# 9_-_STM32F407_Controller.net
KiCad netlist of a schematic drawn in Altium Designer
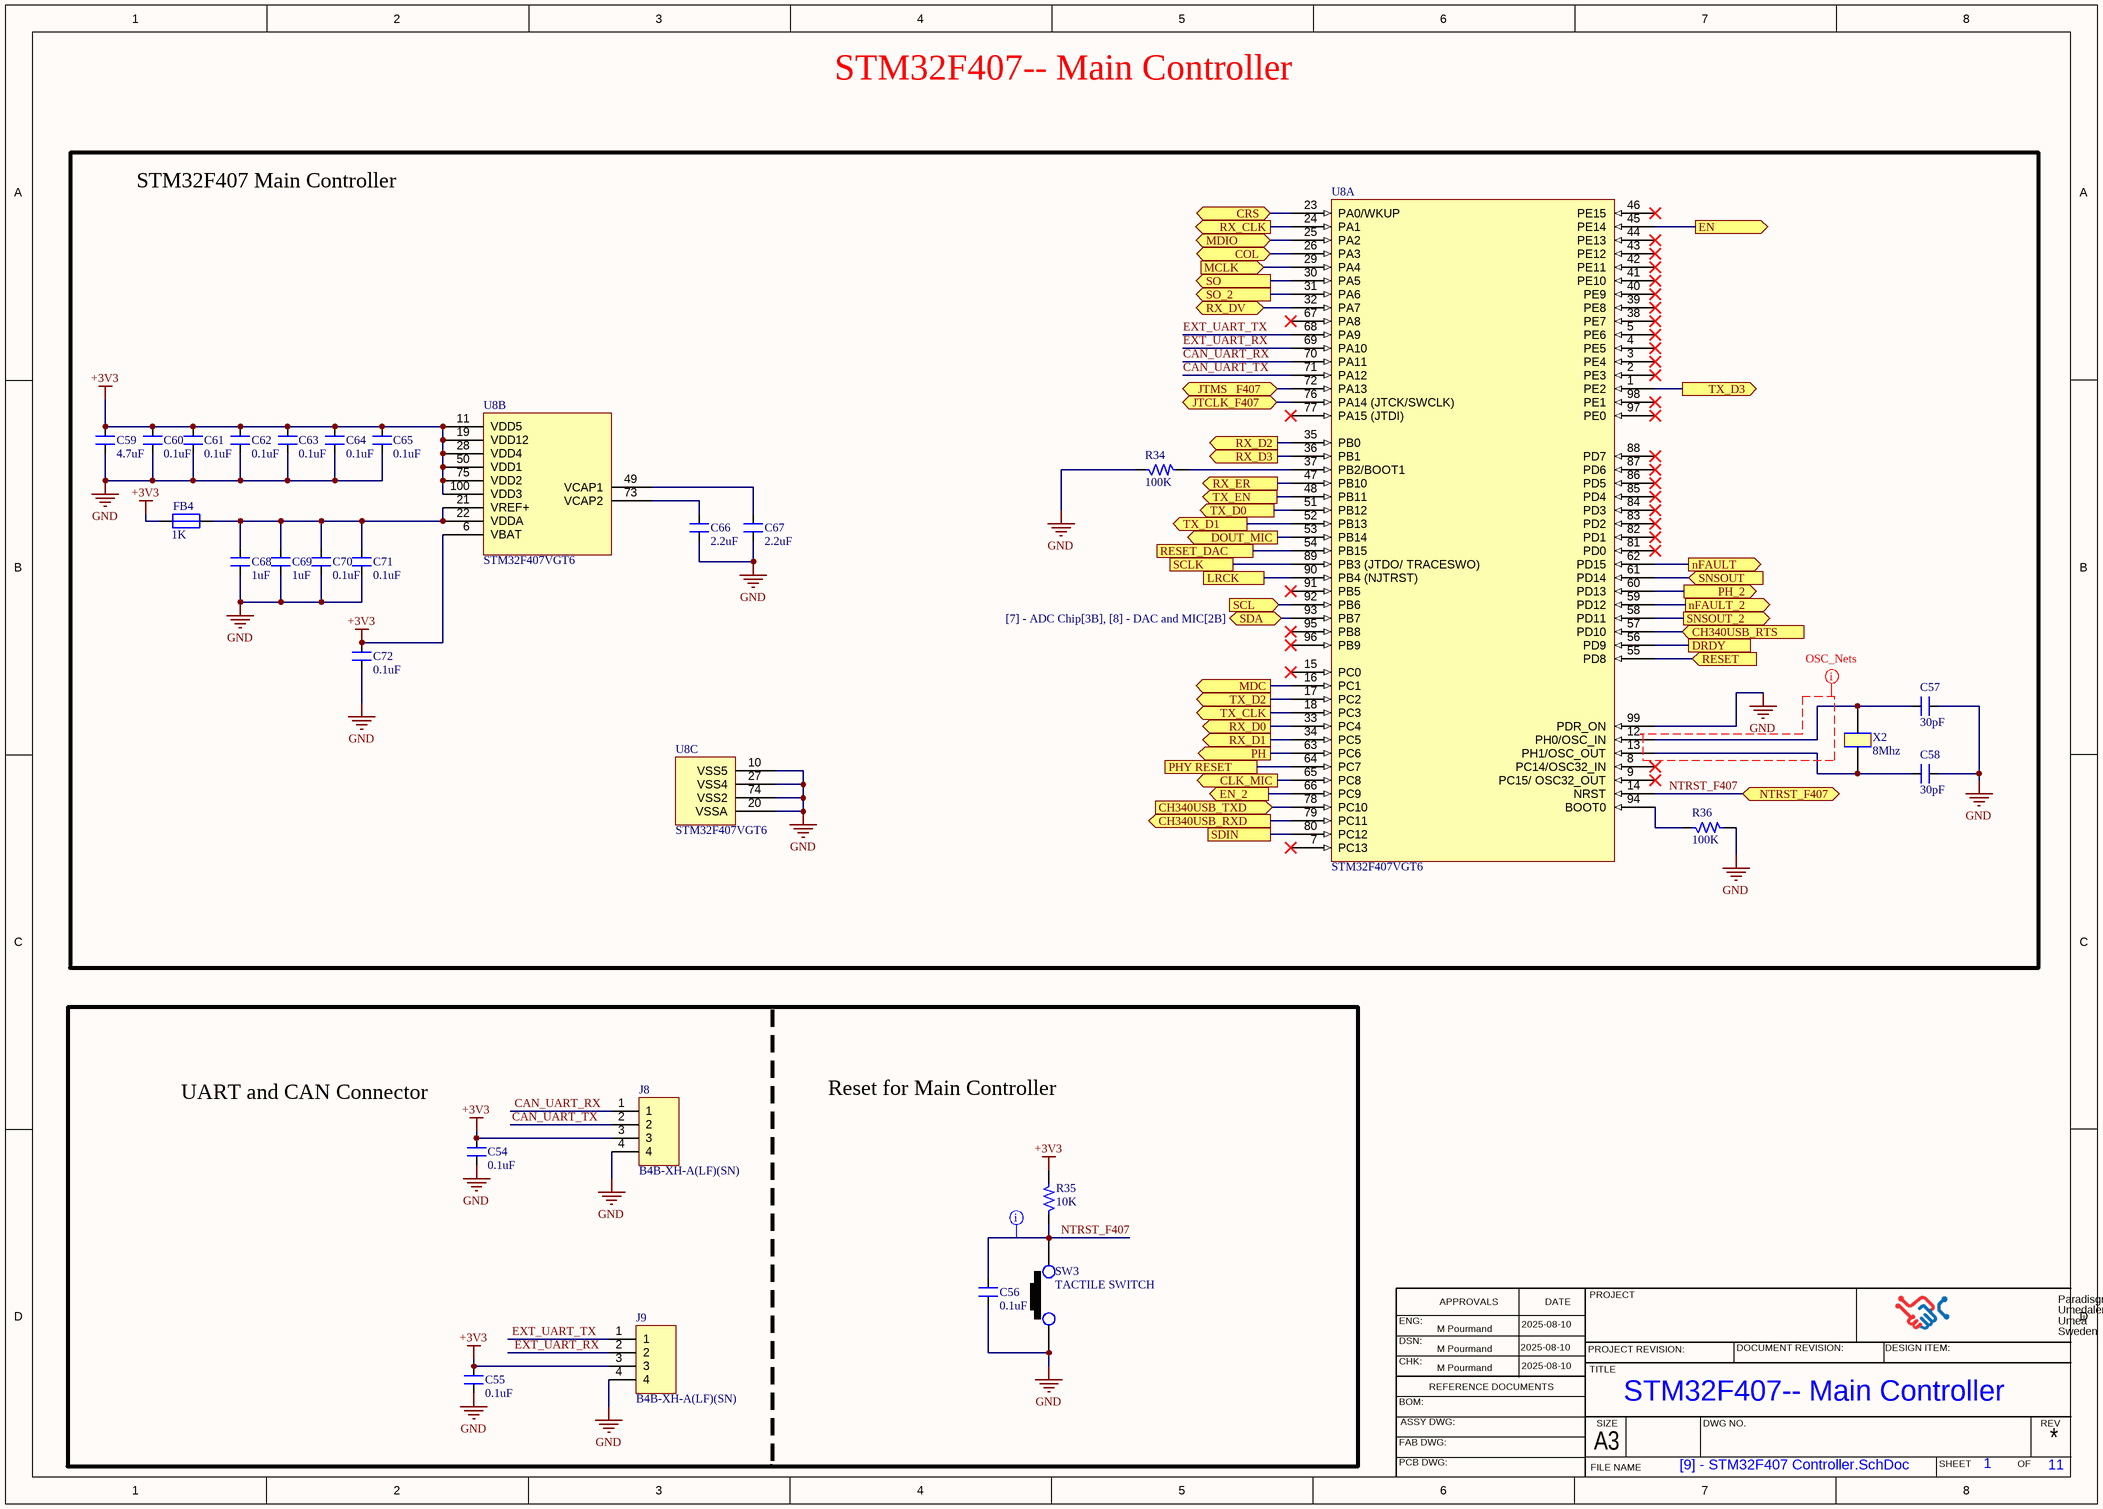
[diagram p0: [9] - STM32F407 Controller.SchDoc]

(export (version "E")
  (design (tool "Eeschema 10.0.6"))
  (components
    (comp (ref "C54")
      (value "0.1uF")
      (footprint "CAP_0805")
      (description "0.1µF ±10% 50V Ceramic Capacitor X7R 0805 (2012 Metric)")
      (fields
        (field (name "MANUFACTURER") "Samsung")
        (field (name "MANUFACTURER PART NUMBER") "CL21B104KBCNNNC")
      )
      (libsource (lib "ESTEEMPCBLIB") (part "CAP_0.1uF-50V-10%-0805"))
    )
    (comp (ref "C55")
      (value "0.1uF")
      (footprint "CAP_0805")
      (description "0.1µF ±10% 50V Ceramic Capacitor X7R 0805 (2012 Metric)")
      (fields
        (field (name "MANUFACTURER") "Samsung")
        (field (name "MANUFACTURER PART NUMBER") "CL21B104KBCNNNC")
      )
      (libsource (lib "ESTEEMPCBLIB") (part "CAP_0.1uF-50V-10%-0805"))
    )
    (comp (ref "C56")
      (value "0.1uF")
      (footprint "CAP_0805")
      (description "0.1µF ±10% 50V Ceramic Capacitor X7R 0805 (2012 Metric)")
      (fields
        (field (name "MANUFACTURER") "Samsung")
        (field (name "MANUFACTURER PART NUMBER") "CL21B104KBCNNNC")
      )
      (libsource (lib "ESTEEMPCBLIB") (part "CAP_0.1uF-50V-10%-0805"))
    )
    (comp (ref "C57")
      (value "30pF")
      (footprint "CAP_0805")
      (description "±10% 50V Ceramic Capacitor C0G, NP0 0805 (2012 Metric)")
      (fields
        (field (name "MANUFACTURER PART NUMBER") "C0805C300K5GAC7800")
        (field (name "MANUFACTURER") "KEMET")
      )
      (libsource (lib "ESTEEMPCBLIB") (part "CAP_30pF-50V-10%-0805"))
    )
    (comp (ref "C58")
      (value "30pF")
      (footprint "CAP_0805")
      (description "±10% 50V Ceramic Capacitor C0G, NP0 0805 (2012 Metric)")
      (fields
        (field (name "MANUFACTURER PART NUMBER") "C0805C300K5GAC7800")
        (field (name "MANUFACTURER") "KEMET")
      )
      (libsource (lib "ESTEEMPCBLIB") (part "CAP_30pF-50V-10%-0805"))
    )
    (comp (ref "C59")
      (value "4.7uF")
      (footprint "CAP_0805")
      (description "4.7µF ±10% 50V Ceramic Capacitor X5R 0805 (2012 Metric)")
      (fields
        (field (name "MANUFACTURER") "Yageo")
        (field (name "MANUFACTURER PART NUMBER") "GRM21BR61H475KE51L")
      )
      (libsource (lib "ESTEEMPCBLIB") (part "CAP_4.7uF-50V-10%-0805"))
    )
    (comp (ref "C60")
      (value "0.1uF")
      (footprint "CAP_0805")
      (description "0.1µF ±10% 50V Ceramic Capacitor X7R 0805 (2012 Metric)")
      (fields
        (field (name "MANUFACTURER") "Samsung")
        (field (name "MANUFACTURER PART NUMBER") "CL21B104KBCNNNC")
      )
      (libsource (lib "ESTEEMPCBLIB") (part "CAP_0.1uF-50V-10%-0805"))
    )
    (comp (ref "C61")
      (value "0.1uF")
      (footprint "CAP_0805")
      (description "0.1µF ±10% 50V Ceramic Capacitor X7R 0805 (2012 Metric)")
      (fields
        (field (name "MANUFACTURER") "Samsung")
        (field (name "MANUFACTURER PART NUMBER") "CL21B104KBCNNNC")
      )
      (libsource (lib "ESTEEMPCBLIB") (part "CAP_0.1uF-50V-10%-0805"))
    )
    (comp (ref "C62")
      (value "0.1uF")
      (footprint "CAP_0805")
      (description "0.1µF ±10% 50V Ceramic Capacitor X7R 0805 (2012 Metric)")
      (fields
        (field (name "MANUFACTURER") "Samsung")
        (field (name "MANUFACTURER PART NUMBER") "CL21B104KBCNNNC")
      )
      (libsource (lib "ESTEEMPCBLIB") (part "CAP_0.1uF-50V-10%-0805"))
    )
    (comp (ref "C63")
      (value "0.1uF")
      (footprint "CAP_0805")
      (description "0.1µF ±10% 50V Ceramic Capacitor X7R 0805 (2012 Metric)")
      (fields
        (field (name "MANUFACTURER") "Samsung")
        (field (name "MANUFACTURER PART NUMBER") "CL21B104KBCNNNC")
      )
      (libsource (lib "ESTEEMPCBLIB") (part "CAP_0.1uF-50V-10%-0805"))
    )
    (comp (ref "C64")
      (value "0.1uF")
      (footprint "CAP_0805")
      (description "0.1µF ±10% 50V Ceramic Capacitor X7R 0805 (2012 Metric)")
      (fields
        (field (name "MANUFACTURER") "Samsung")
        (field (name "MANUFACTURER PART NUMBER") "CL21B104KBCNNNC")
      )
      (libsource (lib "ESTEEMPCBLIB") (part "CAP_0.1uF-50V-10%-0805"))
    )
    (comp (ref "C65")
      (value "0.1uF")
      (footprint "CAP_0805")
      (description "0.1µF ±10% 50V Ceramic Capacitor X7R 0805 (2012 Metric)")
      (fields
        (field (name "MANUFACTURER") "Samsung")
        (field (name "MANUFACTURER PART NUMBER") "CL21B104KBCNNNC")
      )
      (libsource (lib "ESTEEMPCBLIB") (part "CAP_0.1uF-50V-10%-0805"))
    )
    (comp (ref "C66")
      (value "2.2uF")
      (footprint "CAP_0805")
      (description "2.2µF ±10% 25V Ceramic Capacitor X7R 0805 (2012 Metric)")
      (fields
        (field (name "MANUFACTURER") "KEMET")
        (field (name "MANUFACTURER PART NUMBER") "CL21B225KAFNFNE")
      )
      (libsource (lib "ESTEEMPCBLIB") (part "CAP_2.2uF-25V-10%-0805"))
    )
    (comp (ref "C67")
      (value "2.2uF")
      (footprint "CAP_0805")
      (description "2.2µF ±10% 25V Ceramic Capacitor X7R 0805 (2012 Metric)")
      (fields
        (field (name "MANUFACTURER") "KEMET")
        (field (name "MANUFACTURER PART NUMBER") "CL21B225KAFNFNE")
      )
      (libsource (lib "ESTEEMPCBLIB") (part "CAP_2.2uF-25V-10%-0805"))
    )
    (comp (ref "C68")
      (value "1uF")
      (footprint "CAP_0805")
      (description "1µF ±5% 50V Ceramic Capacitor X7R 0805 (2012 Metric)")
      (fields
        (field (name "MANUFACTURER") "Samsung")
        (field (name "MANUFACTURER PART NUMBER") "CC0805JKX7R9BB105")
      )
      (libsource (lib "ESTEEMPCBLIB") (part "CAP_1uF-50V-5%-0805"))
    )
    (comp (ref "C69")
      (value "1uF")
      (footprint "CAP_0805")
      (description "1µF ±5% 50V Ceramic Capacitor X7R 0805 (2012 Metric)")
      (fields
        (field (name "MANUFACTURER") "Samsung")
        (field (name "MANUFACTURER PART NUMBER") "CC0805JKX7R9BB105")
      )
      (libsource (lib "ESTEEMPCBLIB") (part "CAP_1uF-50V-5%-0805"))
    )
    (comp (ref "C70")
      (value "0.1uF")
      (footprint "CAP_0805")
      (description "0.1µF ±10% 50V Ceramic Capacitor X7R 0805 (2012 Metric)")
      (fields
        (field (name "MANUFACTURER") "Samsung")
        (field (name "MANUFACTURER PART NUMBER") "CL21B104KBCNNNC")
      )
      (libsource (lib "ESTEEMPCBLIB") (part "CAP_0.1uF-50V-10%-0805"))
    )
    (comp (ref "C71")
      (value "0.1uF")
      (footprint "CAP_0805")
      (description "0.1µF ±10% 50V Ceramic Capacitor X7R 0805 (2012 Metric)")
      (fields
        (field (name "MANUFACTURER") "Samsung")
        (field (name "MANUFACTURER PART NUMBER") "CL21B104KBCNNNC")
      )
      (libsource (lib "ESTEEMPCBLIB") (part "CAP_0.1uF-50V-10%-0805"))
    )
    (comp (ref "C72")
      (value "0.1uF")
      (footprint "CAP_0805")
      (description "0.1µF ±10% 50V Ceramic Capacitor X7R 0805 (2012 Metric)")
      (fields
        (field (name "MANUFACTURER") "Samsung")
        (field (name "MANUFACTURER PART NUMBER") "CL21B104KBCNNNC")
      )
      (libsource (lib "ESTEEMPCBLIB") (part "CAP_0.1uF-50V-10%-0805"))
    )
    (comp (ref "FB4")
      (value "1K")
      (footprint "IND_0805")
      (description "1 kOhms @ 100MHz 1 Power Line Ferrite Bead 0805 (2012 Metric) 1.6A")
      (fields
        (field (name "MANUFACTURER") "Laird")
        (field (name "MANUFACTURER PART NUMBER") "BLM21SP102SH1D")
      )
      (libsource (lib "ESTEEMPCBLIB") (part "FB_1K-100MHZ-1.6A-0805"))
    )
    (comp (ref "J8")
      (value "B4B-XH-A(LF)(SN)")
      (footprint "CON4_100_B4B-XH-A_TH_ST")
      (description "4 Pins, 1 Row 2.54mm Pitch, straight Connector, male")
      (fields (field (name "MANUFACTURER") "Wurth Electronics") (field (name "MATING PART NUMBER") "XHP-4"))
      (libsource (lib "ESTEEMPCBLIB") (part "CON-PLG_4X1-100-ST-TH"))
    )
    (comp (ref "J9")
      (value "B4B-XH-A(LF)(SN)")
      (footprint "CON4_100_B4B-XH-A_TH_ST")
      (description "4 Pins, 1 Row 2.54mm Pitch, straight Connector, male")
      (fields (field (name "MANUFACTURER") "Wurth Electronics") (field (name "MATING PART NUMBER") "XHP-4"))
      (libsource (lib "ESTEEMPCBLIB") (part "CON-PLG_4X1-100-ST-TH"))
    )
    (comp (ref "R34")
      (value "100K")
      (footprint "RES_0603")
      (description "100 kOhms ±1% 0.1W, 1/10W Chip Resistor 0603 (1608 Metric) Automotive AEC-Q200 Thick Film")
      (fields
        (field (name "MANUFACTURER") "Stackpole Electronics")
        (field (name "MANUFACTURER PART NUMBER") "RMCF0603FT100K")
      )
      (libsource (lib "ESTEEMPCBLIB") (part "RES_100K-0.1W-1%-0603"))
    )
    (comp (ref "R35")
      (value "10K")
      (footprint "RES_0603")
      (description "10 kOhms ±1% 0.1W, 1/10W Chip Resistor 0603 (1608 Metric) Automotive AEC-Q200 Thick Film")
      (fields (field (name "MANUFACTURER") "Walsin") (field (name "MANUFACTURER PART NUMBER") "WR06X1002FTL"))
      (libsource (lib "ESTEEMPCBLIB") (part "RES_10K-0.1W-1%-0603"))
    )
    (comp (ref "R36")
      (value "100K")
      (footprint "RES_0603")
      (description "100 kOhms ±1% 0.1W, 1/10W Chip Resistor 0603 (1608 Metric) Automotive AEC-Q200 Thick Film")
      (fields
        (field (name "MANUFACTURER") "Stackpole Electronics")
        (field (name "MANUFACTURER PART NUMBER") "RMCF0603FT100K")
      )
      (libsource (lib "ESTEEMPCBLIB") (part "RES_100K-0.1W-1%-0603"))
    )
    (comp (ref "SW3")
      (value "TACTILE SWITCH")
      (footprint "SW_342_SMD")
      (description "Tactile Switch SPST-NO Top Actuated Surface Mount")
      (fields
        (field (name "MANUFACTURER") "ITT C&K")
        (field (name "MANUFACTURER PART NUMBER") "RS-282G05A3-SMRT")
      )
      (libsource (lib "ESTEEMPCBLIB") (part "SW1_RS-282G05A3-SMRT-SMD"))
    )
    (comp (ref "U8")
      (value "STM32F407VGT6")
      (footprint "QFN100_19.6_669_58X10_SMD")
      (description "ARM® Cortex®-M4 STM32F4 Microcontroller IC 32-Bit 168MHz 1MB (1M x 8) FLASH 100-LQFP (14x14)")
      (fields (field (name "MANUFACTURER") "STMicroelectronics"))
      (libsource (lib "ESTEEMPCBLIB") (part "IC_STM32F407VGT6"))
    )
    (comp (ref "X2")
      (value "8Mhz")
      (footprint "XTAL_314_240X47_SMD")
      (description "8MHz ±30ppm Crystal 32pF 60 Ohms HC-49/US")
      (fields
        (field (name "MANUFACTURER") "Fox Electronics")
        (field (name "MANUFACTURER PART NUMBER") "ECS-80-32-5PX-TR")
      )
      (libsource (lib "ESTEEMPCBLIB") (part "XTAL_8MHZ-ECS-80-32-5PX-SMD"))
    )
  )
  (nets
    (net (code "1") (name "+3V3") (class "Default")
      (node (ref "C54") (pin "2") (pinfunction "2_2") (pintype "passive"))
      (node (ref "C55") (pin "2") (pinfunction "2_2") (pintype "passive"))
      (node (ref "C59") (pin "2") (pinfunction "2_2") (pintype "passive"))
      (node (ref "C60") (pin "2") (pinfunction "2_2") (pintype "passive"))
      (node (ref "C61") (pin "2") (pinfunction "2_2") (pintype "passive"))
      (node (ref "C62") (pin "2") (pinfunction "2_2") (pintype "passive"))
      (node (ref "C63") (pin "2") (pinfunction "2_2") (pintype "passive"))
      (node (ref "C64") (pin "2") (pinfunction "2_2") (pintype "passive"))
      (node (ref "C65") (pin "2") (pinfunction "2_2") (pintype "passive"))
      (node (ref "C72") (pin "2") (pinfunction "2_2") (pintype "passive"))
      (node (ref "FB4") (pin "1") (pinfunction "1_1") (pintype "passive"))
      (node (ref "J8") (pin "3") (pinfunction "3_3") (pintype "passive"))
      (node (ref "J9") (pin "3") (pinfunction "3_3") (pintype "passive"))
      (node (ref "R35") (pin "2") (pinfunction "2_2") (pintype "passive"))
      (node (ref "U8") (pin "100") (pinfunction "VDD3_100") (pintype "passive"))
      (node (ref "U8") (pin "11") (pinfunction "VDD5_11") (pintype "passive"))
      (node (ref "U8") (pin "19") (pinfunction "VDD12_19") (pintype "passive"))
      (node (ref "U8") (pin "28") (pinfunction "VDD4_28") (pintype "passive"))
      (node (ref "U8") (pin "50") (pinfunction "VDD1_50") (pintype "passive"))
      (node (ref "U8") (pin "6") (pinfunction "VBAT_6") (pintype "passive"))
      (node (ref "U8") (pin "75") (pinfunction "VDD2_75") (pintype "passive"))
    )
    (net (code "2") (name "/CAN_UART_RX") (class "Default")
      (node (ref "J8") (pin "1") (pinfunction "1_1") (pintype "passive"))
      (node (ref "U8") (pin "70") (pinfunction "PA11_70") (pintype "input"))
    )
    (net (code "3") (name "/CAN_UART_TX") (class "Default")
      (node (ref "J8") (pin "2") (pinfunction "2_2") (pintype "passive"))
      (node (ref "U8") (pin "71") (pinfunction "PA12_71") (pintype "input"))
    )
    (net (code "4") (name "/CH340USB_RTS") (class "Default")
      (node (ref "U8") (pin "57") (pinfunction "PD10_57") (pintype "input"))
    )
    (net (code "5") (name "/CH340USB_RXD") (class "Default")
      (node (ref "U8") (pin "79") (pinfunction "PC11_79") (pintype "input"))
    )
    (net (code "6") (name "/CH340USB_TXD") (class "Default")
      (node (ref "U8") (pin "78") (pinfunction "PC10_78") (pintype "input"))
    )
    (net (code "7") (name "/CLK_MIC") (class "Default")
      (node (ref "U8") (pin "65") (pinfunction "PC8_65") (pintype "input"))
    )
    (net (code "8") (name "/COL") (class "Default")
      (node (ref "U8") (pin "26") (pinfunction "PA3_26") (pintype "input"))
    )
    (net (code "9") (name "/CRS") (class "Default")
      (node (ref "U8") (pin "23") (pinfunction "PA0/WKUP_23") (pintype "input"))
    )
    (net (code "10") (name "/DOUT_MIC") (class "Default")
      (node (ref "U8") (pin "53") (pinfunction "PB14_53") (pintype "input"))
    )
    (net (code "11") (name "/DRDY") (class "Default")
      (node (ref "U8") (pin "56") (pinfunction "PD9_56") (pintype "input"))
    )
    (net (code "12") (name "/EN") (class "Default")
      (node (ref "U8") (pin "45") (pinfunction "PE14_45") (pintype "input"))
    )
    (net (code "13") (name "/EN_2") (class "Default")
      (node (ref "U8") (pin "66") (pinfunction "PC9_66") (pintype "input"))
    )
    (net (code "14") (name "/EXT_UART_RX") (class "Default")
      (node (ref "J9") (pin "2") (pinfunction "2_2") (pintype "passive"))
      (node (ref "U8") (pin "69") (pinfunction "PA10_69") (pintype "input"))
    )
    (net (code "15") (name "/EXT_UART_TX") (class "Default")
      (node (ref "J9") (pin "1") (pinfunction "1_1") (pintype "passive"))
      (node (ref "U8") (pin "68") (pinfunction "PA9_68") (pintype "input"))
    )
    (net (code "16") (name "/JTCLK_F407") (class "Default")
      (node (ref "U8") (pin "76") (pinfunction "PA14_(JTCK/SWCLK)_76") (pintype "input"))
    )
    (net (code "17") (name "/JTMS   F407") (class "Default")
      (node (ref "U8") (pin "72") (pinfunction "PA13_72") (pintype "input"))
    )
    (net (code "18") (name "/LRCK") (class "Default")
      (node (ref "U8") (pin "90") (pinfunction "PB4_(NJTRST)_90") (pintype "input"))
    )
    (net (code "19") (name "/MCLK") (class "Default")
      (node (ref "U8") (pin "29") (pinfunction "PA4_29") (pintype "input"))
    )
    (net (code "20") (name "/MDC") (class "Default")
      (node (ref "U8") (pin "16") (pinfunction "PC1_16") (pintype "input"))
    )
    (net (code "21") (name "/MDIO") (class "Default")
      (node (ref "U8") (pin "25") (pinfunction "PA2_25") (pintype "input"))
    )
    (net (code "22") (name "/NTRST_F407") (class "Default")
      (node (ref "C56") (pin "2") (pinfunction "2_2") (pintype "passive"))
      (node (ref "R35") (pin "1") (pinfunction "1_1") (pintype "passive"))
      (node (ref "SW3") (pin "2") (pinfunction "2_2") (pintype "passive"))
      (node (ref "U8") (pin "14") (pinfunction "NRST_14") (pintype "input"))
    )
    (net (code "23") (name "/PH") (class "Default")
      (node (ref "U8") (pin "63") (pinfunction "PC6_63") (pintype "input"))
    )
    (net (code "24") (name "/PHY RESET") (class "Default")
      (node (ref "U8") (pin "64") (pinfunction "PC7_64") (pintype "input"))
    )
    (net (code "25") (name "/PH_2") (class "Default")
      (node (ref "U8") (pin "60") (pinfunction "PD13_60") (pintype "input"))
    )
    (net (code "26") (name "/RESET") (class "Default")
      (node (ref "U8") (pin "55") (pinfunction "PD8_55") (pintype "input"))
    )
    (net (code "27") (name "/RESET_DAC") (class "Default")
      (node (ref "U8") (pin "54") (pinfunction "PB15_54") (pintype "input"))
    )
    (net (code "28") (name "/RX_CLK") (class "Default")
      (node (ref "U8") (pin "24") (pinfunction "PA1_24") (pintype "input"))
    )
    (net (code "29") (name "/RX_D0") (class "Default")
      (node (ref "U8") (pin "33") (pinfunction "PC4_33") (pintype "input"))
    )
    (net (code "30") (name "/RX_D1") (class "Default")
      (node (ref "U8") (pin "34") (pinfunction "PC5_34") (pintype "input"))
    )
    (net (code "31") (name "/RX_D2") (class "Default")
      (node (ref "U8") (pin "35") (pinfunction "PB0_35") (pintype "input"))
    )
    (net (code "32") (name "/RX_D3") (class "Default")
      (node (ref "U8") (pin "36") (pinfunction "PB1_36") (pintype "input"))
    )
    (net (code "33") (name "/RX_DV") (class "Default")
      (node (ref "U8") (pin "32") (pinfunction "PA7_32") (pintype "input"))
    )
    (net (code "34") (name "/RX_ER") (class "Default")
      (node (ref "U8") (pin "47") (pinfunction "PB10_47") (pintype "input"))
    )
    (net (code "35") (name "/SCL") (class "Default")
      (node (ref "U8") (pin "92") (pinfunction "PB6_92") (pintype "input"))
    )
    (net (code "36") (name "/SCLK") (class "Default")
      (node (ref "U8") (pin "89") (pinfunction "PB3_(JTDO/_TRACESWO)_89") (pintype "input"))
    )
    (net (code "37") (name "/SDA") (class "Default")
      (node (ref "U8") (pin "93") (pinfunction "PB7_93") (pintype "input"))
    )
    (net (code "38") (name "/SDIN") (class "Default")
      (node (ref "U8") (pin "80") (pinfunction "PC12_80") (pintype "input"))
    )
    (net (code "39") (name "/SNSOUT") (class "Default")
      (node (ref "U8") (pin "61") (pinfunction "PD14_61") (pintype "input"))
    )
    (net (code "40") (name "/SNSOUT_2") (class "Default")
      (node (ref "U8") (pin "58") (pinfunction "PD11_58") (pintype "input"))
    )
    (net (code "41") (name "/SO") (class "Default")
      (node (ref "U8") (pin "30") (pinfunction "PA5_30") (pintype "input"))
    )
    (net (code "42") (name "/SO_2") (class "Default")
      (node (ref "U8") (pin "31") (pinfunction "PA6_31") (pintype "input"))
    )
    (net (code "43") (name "/TX_CLK") (class "Default")
      (node (ref "U8") (pin "18") (pinfunction "PC3_18") (pintype "input"))
    )
    (net (code "44") (name "/TX_D0") (class "Default")
      (node (ref "U8") (pin "51") (pinfunction "PB12_51") (pintype "input"))
    )
    (net (code "45") (name "/TX_D1") (class "Default")
      (node (ref "U8") (pin "52") (pinfunction "PB13_52") (pintype "input"))
    )
    (net (code "46") (name "/TX_D2") (class "Default")
      (node (ref "U8") (pin "17") (pinfunction "PC2_17") (pintype "input"))
    )
    (net (code "47") (name "/TX_D3") (class "Default")
      (node (ref "U8") (pin "1") (pinfunction "PE2_1") (pintype "input"))
    )
    (net (code "48") (name "/TX_EN") (class "Default")
      (node (ref "U8") (pin "48") (pinfunction "PB11_48") (pintype "input"))
    )
    (net (code "49") (name "/nFAULT") (class "Default")
      (node (ref "U8") (pin "62") (pinfunction "PD15_62") (pintype "input"))
    )
    (net (code "50") (name "/nFAULT_2") (class "Default")
      (node (ref "U8") (pin "59") (pinfunction "PD12_59") (pintype "input"))
    )
    (net (code "51") (name "GND") (class "Default")
      (node (ref "C54") (pin "1") (pinfunction "1_1") (pintype "passive"))
      (node (ref "C55") (pin "1") (pinfunction "1_1") (pintype "passive"))
      (node (ref "C56") (pin "1") (pinfunction "1_1") (pintype "passive"))
      (node (ref "C57") (pin "2") (pinfunction "2_2") (pintype "passive"))
      (node (ref "C58") (pin "2") (pinfunction "2_2") (pintype "passive"))
      (node (ref "C59") (pin "1") (pinfunction "1_1") (pintype "passive"))
      (node (ref "C60") (pin "1") (pinfunction "1_1") (pintype "passive"))
      (node (ref "C61") (pin "1") (pinfunction "1_1") (pintype "passive"))
      (node (ref "C62") (pin "1") (pinfunction "1_1") (pintype "passive"))
      (node (ref "C63") (pin "1") (pinfunction "1_1") (pintype "passive"))
      (node (ref "C64") (pin "1") (pinfunction "1_1") (pintype "passive"))
      (node (ref "C65") (pin "1") (pinfunction "1_1") (pintype "passive"))
      (node (ref "C66") (pin "1") (pinfunction "1_1") (pintype "passive"))
      (node (ref "C67") (pin "1") (pinfunction "1_1") (pintype "passive"))
      (node (ref "C68") (pin "1") (pinfunction "1_1") (pintype "passive"))
      (node (ref "C69") (pin "1") (pinfunction "1_1") (pintype "passive"))
      (node (ref "C70") (pin "1") (pinfunction "1_1") (pintype "passive"))
      (node (ref "C71") (pin "1") (pinfunction "1_1") (pintype "passive"))
      (node (ref "C72") (pin "1") (pinfunction "1_1") (pintype "passive"))
      (node (ref "J8") (pin "4") (pinfunction "4_4") (pintype "passive"))
      (node (ref "J9") (pin "4") (pinfunction "4_4") (pintype "passive"))
      (node (ref "R34") (pin "1") (pinfunction "1_1") (pintype "passive"))
      (node (ref "R36") (pin "2") (pinfunction "2_2") (pintype "passive"))
      (node (ref "SW3") (pin "1") (pinfunction "1_1") (pintype "passive"))
      (node (ref "U8") (pin "10") (pinfunction "VSS5_10") (pintype "passive"))
      (node (ref "U8") (pin "20") (pinfunction "VSSA_20") (pintype "passive"))
      (node (ref "U8") (pin "27") (pinfunction "VSS4_27") (pintype "passive"))
      (node (ref "U8") (pin "74") (pinfunction "VSS2_74") (pintype "passive"))
      (node (ref "U8") (pin "99") (pinfunction "PDR_ON_99") (pintype "input"))
    )
    (net (code "52") (name "Net-(U8A-BOOT0)") (class "Default")
      (node (ref "R36") (pin "1") (pinfunction "1_1") (pintype "passive"))
      (node (ref "U8") (pin "94") (pinfunction "BOOT0_94") (pintype "input"))
    )
    (net (code "53") (name "Net-(U8A-PB2{slash}BOOT1)") (class "Default")
      (node (ref "R34") (pin "2") (pinfunction "2_2") (pintype "passive"))
      (node (ref "U8") (pin "37") (pinfunction "PB2/BOOT1_37") (pintype "input"))
    )
    (net (code "54") (name "Net-(U8A-PH0{slash}OSC_IN)") (class "Default")
      (node (ref "C57") (pin "1") (pinfunction "1_1") (pintype "passive"))
      (node (ref "U8") (pin "12") (pinfunction "PH0/OSC_IN_12") (pintype "input"))
      (node (ref "X2") (pin "2") (pinfunction "2_2") (pintype "passive"))
    )
    (net (code "55") (name "Net-(U8A-PH1{slash}OSC_OUT)") (class "Default")
      (node (ref "C58") (pin "1") (pinfunction "1_1") (pintype "passive"))
      (node (ref "U8") (pin "13") (pinfunction "PH1/OSC_OUT_13") (pintype "input"))
      (node (ref "X2") (pin "1") (pinfunction "1_1") (pintype "passive"))
    )
    (net (code "56") (name "Net-(U8B-VCAP1)") (class "Default")
      (node (ref "C67") (pin "2") (pinfunction "2_2") (pintype "passive"))
      (node (ref "U8") (pin "49") (pinfunction "VCAP1_49") (pintype "passive"))
    )
    (net (code "57") (name "Net-(U8B-VCAP2)") (class "Default")
      (node (ref "C66") (pin "2") (pinfunction "2_2") (pintype "passive"))
      (node (ref "U8") (pin "73") (pinfunction "VCAP2_73") (pintype "passive"))
    )
    (net (code "58") (name "Net-(U8B-VDDA)") (class "Default")
      (node (ref "C68") (pin "2") (pinfunction "2_2") (pintype "passive"))
      (node (ref "C69") (pin "2") (pinfunction "2_2") (pintype "passive"))
      (node (ref "C70") (pin "2") (pinfunction "2_2") (pintype "passive"))
      (node (ref "C71") (pin "2") (pinfunction "2_2") (pintype "passive"))
      (node (ref "FB4") (pin "2") (pinfunction "2_2") (pintype "passive"))
      (node (ref "U8") (pin "21") (pinfunction "VREF+_21") (pintype "passive"))
      (node (ref "U8") (pin "22") (pinfunction "VDDA_22") (pintype "passive"))
    )
    (net (code "59") (name "unconnected-(U8A-PA8-Pad67)") (class "Default")
      (node (ref "U8") (pin "67") (pinfunction "PA8_67") (pintype "input+no_connect"))
    )
    (net (code "60") (name "unconnected-(U8A-PA15_(JTDI)-Pad77)") (class "Default")
      (node (ref "U8") (pin "77") (pinfunction "PA15_(JTDI)_77") (pintype "input+no_connect"))
    )
    (net (code "61") (name "unconnected-(U8A-PB5-Pad91)") (class "Default")
      (node (ref "U8") (pin "91") (pinfunction "PB5_91") (pintype "input+no_connect"))
    )
    (net (code "62") (name "unconnected-(U8A-PB8-Pad95)") (class "Default")
      (node (ref "U8") (pin "95") (pinfunction "PB8_95") (pintype "input+no_connect"))
    )
    (net (code "63") (name "unconnected-(U8A-PB9-Pad96)") (class "Default")
      (node (ref "U8") (pin "96") (pinfunction "PB9_96") (pintype "input+no_connect"))
    )
    (net (code "64") (name "unconnected-(U8A-PC0-Pad15)") (class "Default")
      (node (ref "U8") (pin "15") (pinfunction "PC0_15") (pintype "input+no_connect"))
    )
    (net (code "65") (name "unconnected-(U8A-PC13-Pad7)") (class "Default")
      (node (ref "U8") (pin "7") (pinfunction "PC13_7") (pintype "input+no_connect"))
    )
    (net (code "66") (name "unconnected-(U8A-PC14{slash}OSC32_IN-Pad8)") (class "Default")
      (node (ref "U8") (pin "8") (pinfunction "PC14/OSC32_IN_8") (pintype "input+no_connect"))
    )
    (net (code "67") (name "unconnected-(U8A-PC15{slash}_OSC32_OUT-Pad9)") (class "Default")
      (node (ref "U8") (pin "9") (pinfunction "PC15/_OSC32_OUT_9") (pintype "input+no_connect"))
    )
    (net (code "68") (name "unconnected-(U8A-PD0-Pad81)") (class "Default")
      (node (ref "U8") (pin "81") (pinfunction "PD0_81") (pintype "input+no_connect"))
    )
    (net (code "69") (name "unconnected-(U8A-PD1-Pad82)") (class "Default")
      (node (ref "U8") (pin "82") (pinfunction "PD1_82") (pintype "input+no_connect"))
    )
    (net (code "70") (name "unconnected-(U8A-PD2-Pad83)") (class "Default")
      (node (ref "U8") (pin "83") (pinfunction "PD2_83") (pintype "input+no_connect"))
    )
    (net (code "71") (name "unconnected-(U8A-PD3-Pad84)") (class "Default")
      (node (ref "U8") (pin "84") (pinfunction "PD3_84") (pintype "input+no_connect"))
    )
    (net (code "72") (name "unconnected-(U8A-PD4-Pad85)") (class "Default")
      (node (ref "U8") (pin "85") (pinfunction "PD4_85") (pintype "input+no_connect"))
    )
    (net (code "73") (name "unconnected-(U8A-PD5-Pad86)") (class "Default")
      (node (ref "U8") (pin "86") (pinfunction "PD5_86") (pintype "input+no_connect"))
    )
    (net (code "74") (name "unconnected-(U8A-PD6-Pad87)") (class "Default")
      (node (ref "U8") (pin "87") (pinfunction "PD6_87") (pintype "input+no_connect"))
    )
    (net (code "75") (name "unconnected-(U8A-PD7-Pad88)") (class "Default")
      (node (ref "U8") (pin "88") (pinfunction "PD7_88") (pintype "input+no_connect"))
    )
    (net (code "76") (name "unconnected-(U8A-PE0-Pad97)") (class "Default")
      (node (ref "U8") (pin "97") (pinfunction "PE0_97") (pintype "input+no_connect"))
    )
    (net (code "77") (name "unconnected-(U8A-PE1-Pad98)") (class "Default")
      (node (ref "U8") (pin "98") (pinfunction "PE1_98") (pintype "input+no_connect"))
    )
    (net (code "78") (name "unconnected-(U8A-PE3-Pad2)") (class "Default")
      (node (ref "U8") (pin "2") (pinfunction "PE3_2") (pintype "input+no_connect"))
    )
    (net (code "79") (name "unconnected-(U8A-PE4-Pad3)") (class "Default")
      (node (ref "U8") (pin "3") (pinfunction "PE4_3") (pintype "input+no_connect"))
    )
    (net (code "80") (name "unconnected-(U8A-PE5-Pad4)") (class "Default")
      (node (ref "U8") (pin "4") (pinfunction "PE5_4") (pintype "input+no_connect"))
    )
    (net (code "81") (name "unconnected-(U8A-PE6-Pad5)") (class "Default")
      (node (ref "U8") (pin "5") (pinfunction "PE6_5") (pintype "input+no_connect"))
    )
    (net (code "82") (name "unconnected-(U8A-PE7-Pad38)") (class "Default")
      (node (ref "U8") (pin "38") (pinfunction "PE7_38") (pintype "input+no_connect"))
    )
    (net (code "83") (name "unconnected-(U8A-PE8-Pad39)") (class "Default")
      (node (ref "U8") (pin "39") (pinfunction "PE8_39") (pintype "input+no_connect"))
    )
    (net (code "84") (name "unconnected-(U8A-PE9-Pad40)") (class "Default")
      (node (ref "U8") (pin "40") (pinfunction "PE9_40") (pintype "input+no_connect"))
    )
    (net (code "85") (name "unconnected-(U8A-PE10-Pad41)") (class "Default")
      (node (ref "U8") (pin "41") (pinfunction "PE10_41") (pintype "input+no_connect"))
    )
    (net (code "86") (name "unconnected-(U8A-PE11-Pad42)") (class "Default")
      (node (ref "U8") (pin "42") (pinfunction "PE11_42") (pintype "input+no_connect"))
    )
    (net (code "87") (name "unconnected-(U8A-PE12-Pad43)") (class "Default")
      (node (ref "U8") (pin "43") (pinfunction "PE12_43") (pintype "input+no_connect"))
    )
    (net (code "88") (name "unconnected-(U8A-PE13-Pad44)") (class "Default")
      (node (ref "U8") (pin "44") (pinfunction "PE13_44") (pintype "input+no_connect"))
    )
    (net (code "89") (name "unconnected-(U8A-PE15-Pad46)") (class "Default")
      (node (ref "U8") (pin "46") (pinfunction "PE15_46") (pintype "input+no_connect"))
    )
  )
)
